# Sensor.net
KiCad netlist of a schematic drawn in Altium Designer
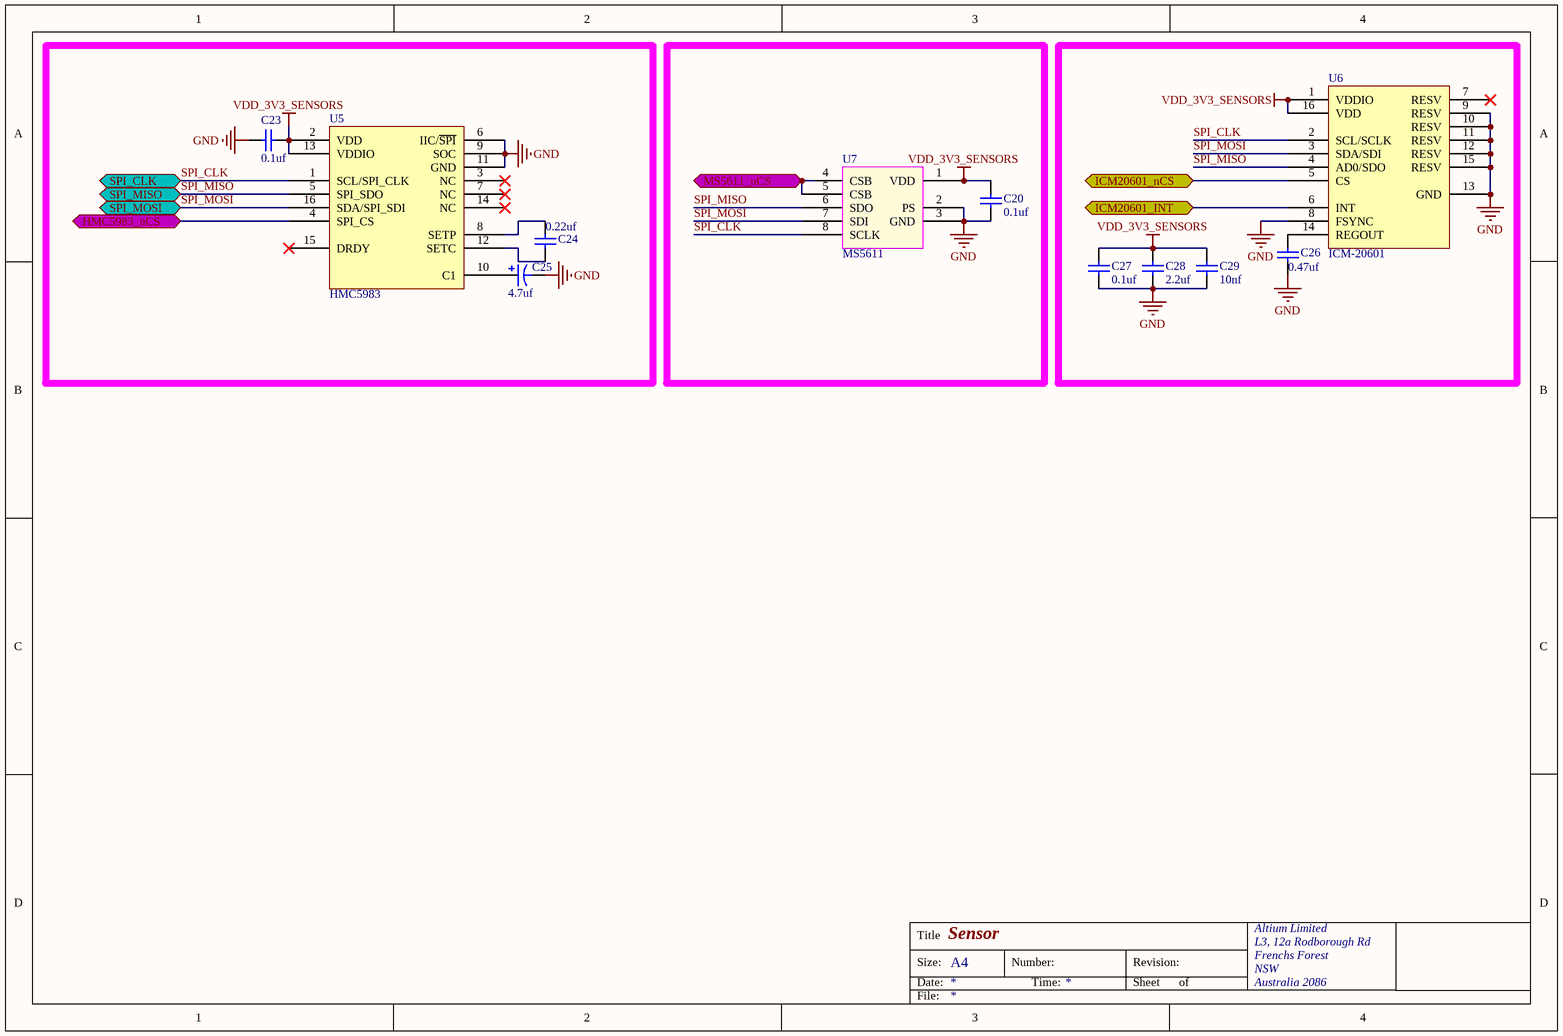
[diagram p0: Sensor.SchDoc]

(export (version "E")
  (design (tool "Eeschema 10.0.6"))
  (components
    (comp (ref "C20")
      (value "0.1uf")
      (footprint "0603AC")
      (description "Capacitor")
      (fields (field (name "Comment") "Cap1") (field (name "PUBLISHER") "Altium Limited"))
      (libsource (lib "Component") (part "Cap1"))
    )
    (comp (ref "C23")
      (value "0.1uf")
      (footprint "0603AC")
      (description "Capacitor")
      (fields (field (name "Comment") "Cap1") (field (name "PUBLISHER") "Altium Limited"))
      (libsource (lib "Component") (part "Cap1"))
    )
    (comp (ref "C24")
      (value "0.22uf")
      (footprint "0603AC")
      (description "Capacitor")
      (fields (field (name "Comment") "Cap1") (field (name "PUBLISHER") "Altium Limited"))
      (libsource (lib "Component") (part "Cap1"))
    )
    (comp (ref "C25")
      (value "4.7uf")
      (footprint "0603AC")
      (description "Polarized Capacitor (Axial)")
      (fields (field (name "Comment") "Cap Pol1") (field (name "PUBLISHER") "Altium Limited"))
      (libsource (lib "Component") (part "Cap Pol1"))
    )
    (comp (ref "C26")
      (value "0.47uf")
      (footprint "0603AC")
      (description "Capacitor")
      (fields (field (name "Comment") "Cap1") (field (name "PUBLISHER") "Altium Limited"))
      (libsource (lib "Component") (part "Cap1"))
    )
    (comp (ref "C27")
      (value "0.1uf")
      (footprint "0603AC")
      (description "Capacitor")
      (fields (field (name "Comment") "Cap1") (field (name "PUBLISHER") "Altium Limited"))
      (libsource (lib "Component") (part "Cap1"))
    )
    (comp (ref "C28")
      (value "2.2uf")
      (footprint "0603AC")
      (description "Capacitor")
      (fields (field (name "Comment") "Cap1") (field (name "PUBLISHER") "Altium Limited"))
      (libsource (lib "Component") (part "Cap1"))
    )
    (comp (ref "C29")
      (value "10nf")
      (footprint "0603AC")
      (description "Capacitor")
      (fields (field (name "Comment") "Cap1") (field (name "PUBLISHER") "Altium Limited"))
      (libsource (lib "Component") (part "Cap1"))
    )
    (comp (ref "U5") (value "HMC5983") (footprint "LPCC-16PIN") (libsource (lib "Sensor") (part "HMC5983")))
    (comp (ref "U6")
      (value "ICM-20601")
      (footprint "LGA-16PIN")
      (libsource (lib "Sensor") (part "ICM-20601"))
    )
    (comp (ref "U7") (value "MS5611") (footprint "MS5611") (libsource (lib "Sensor") (part "MS5611")))
  )
  (nets
    (net (code "1") (name "/HMC5983_nCS") (class "Default")
      (node (ref "U5") (pin "4") (pinfunction "SPI_CS_4") (pintype "passive"))
    )
    (net (code "2") (name "/ICM20601_INT") (class "Default")
      (node (ref "U6") (pin "6") (pinfunction "INT_6") (pintype "passive"))
    )
    (net (code "3") (name "/ICM20601_nCS") (class "Default")
      (node (ref "U6") (pin "5") (pinfunction "CS_5") (pintype "passive"))
    )
    (net (code "4") (name "/MS5611_nCS") (class "Default")
      (node (ref "U7") (pin "4") (pinfunction "CSB_4") (pintype "passive"))
      (node (ref "U7") (pin "5") (pinfunction "CSB_5") (pintype "passive"))
    )
    (net (code "5") (name "/SPI_CLK") (class "Default")
      (node (ref "U5") (pin "1") (pinfunction "SCL/SPI_CLK_1") (pintype "passive"))
      (node (ref "U6") (pin "2") (pinfunction "SCL/SCLK_2") (pintype "passive"))
      (node (ref "U7") (pin "8") (pinfunction "SCLK_8") (pintype "passive"))
    )
    (net (code "6") (name "/SPI_MISO") (class "Default")
      (node (ref "U5") (pin "5") (pinfunction "SPI_SDO_5") (pintype "passive"))
      (node (ref "U6") (pin "4") (pinfunction "AD0/SDO_4") (pintype "passive"))
      (node (ref "U7") (pin "6") (pinfunction "SDO_6") (pintype "passive"))
    )
    (net (code "7") (name "/SPI_MOSI") (class "Default")
      (node (ref "U5") (pin "16") (pinfunction "SDA/SPI_SDI_16") (pintype "passive"))
      (node (ref "U6") (pin "3") (pinfunction "SDA/SDI_3") (pintype "passive"))
      (node (ref "U7") (pin "7") (pinfunction "SDI_7") (pintype "passive"))
    )
    (net (code "8") (name "GND") (class "Default")
      (node (ref "C20") (pin "2") (pinfunction "2_2") (pintype "passive"))
      (node (ref "C23") (pin "2") (pinfunction "2_2") (pintype "passive"))
      (node (ref "C25") (pin "2") (pinfunction "2_2") (pintype "passive"))
      (node (ref "C26") (pin "1") (pinfunction "1_1") (pintype "passive"))
      (node (ref "C27") (pin "2") (pinfunction "2_2") (pintype "passive"))
      (node (ref "C28") (pin "2") (pinfunction "2_2") (pintype "passive"))
      (node (ref "C29") (pin "2") (pinfunction "2_2") (pintype "passive"))
      (node (ref "U5") (pin "11") (pinfunction "GND_11") (pintype "passive"))
      (node (ref "U5") (pin "6") (pinfunction "IIC/~{SPI}_6") (pintype "passive"))
      (node (ref "U5") (pin "9") (pinfunction "SOC_9") (pintype "passive"))
      (node (ref "U6") (pin "10") (pinfunction "RESV_10") (pintype "passive"))
      (node (ref "U6") (pin "11") (pinfunction "RESV_11") (pintype "passive"))
      (node (ref "U6") (pin "12") (pinfunction "RESV_12") (pintype "passive"))
      (node (ref "U6") (pin "13") (pinfunction "GND_13") (pintype "passive"))
      (node (ref "U6") (pin "15") (pinfunction "RESV_15") (pintype "passive"))
      (node (ref "U6") (pin "8") (pinfunction "FSYNC_8") (pintype "passive"))
      (node (ref "U6") (pin "9") (pinfunction "RESV_9") (pintype "passive"))
      (node (ref "U7") (pin "2") (pinfunction "PS_2") (pintype "passive"))
      (node (ref "U7") (pin "3") (pinfunction "GND_3") (pintype "passive"))
    )
    (net (code "9") (name "Net-(U5-C1)") (class "Default")
      (node (ref "C25") (pin "1") (pinfunction "1_1") (pintype "passive"))
      (node (ref "U5") (pin "10") (pinfunction "C1_10") (pintype "passive"))
    )
    (net (code "10") (name "Net-(U5-SETC)") (class "Default")
      (node (ref "C24") (pin "1") (pinfunction "1_1") (pintype "passive"))
      (node (ref "U5") (pin "12") (pinfunction "SETC_12") (pintype "passive"))
    )
    (net (code "11") (name "Net-(U5-SETP)") (class "Default")
      (node (ref "C24") (pin "2") (pinfunction "2_2") (pintype "passive"))
      (node (ref "U5") (pin "8") (pinfunction "SETP_8") (pintype "passive"))
    )
    (net (code "12") (name "Net-(U6-REGOUT)") (class "Default")
      (node (ref "C26") (pin "2") (pinfunction "2_2") (pintype "passive"))
      (node (ref "U6") (pin "14") (pinfunction "REGOUT_14") (pintype "passive"))
    )
    (net (code "13") (name "VDD_3V3_SENSORS") (class "Default")
      (node (ref "C20") (pin "1") (pinfunction "1_1") (pintype "passive"))
      (node (ref "C23") (pin "1") (pinfunction "1_1") (pintype "passive"))
      (node (ref "C27") (pin "1") (pinfunction "1_1") (pintype "passive"))
      (node (ref "C28") (pin "1") (pinfunction "1_1") (pintype "passive"))
      (node (ref "C29") (pin "1") (pinfunction "1_1") (pintype "passive"))
      (node (ref "U5") (pin "13") (pinfunction "VDDIO_13") (pintype "passive"))
      (node (ref "U5") (pin "2") (pinfunction "VDD_2") (pintype "passive"))
      (node (ref "U6") (pin "1") (pinfunction "VDDIO_1") (pintype "passive"))
      (node (ref "U6") (pin "16") (pinfunction "VDD_16") (pintype "passive"))
      (node (ref "U7") (pin "1") (pinfunction "VDD_1") (pintype "passive"))
    )
    (net (code "14") (name "unconnected-(U5-DRDY-Pad15)") (class "Default")
      (node (ref "U5") (pin "15") (pinfunction "DRDY_15") (pintype "passive+no_connect"))
    )
    (net (code "15") (name "unconnected-(U5-NC-Pad3)") (class "Default")
      (node (ref "U5") (pin "3") (pinfunction "NC_3") (pintype "passive+no_connect"))
    )
    (net (code "16") (name "unconnected-(U5-NC-Pad7)") (class "Default")
      (node (ref "U5") (pin "7") (pinfunction "NC_7") (pintype "passive+no_connect"))
    )
    (net (code "17") (name "unconnected-(U5-NC-Pad14)") (class "Default")
      (node (ref "U5") (pin "14") (pinfunction "NC_14") (pintype "passive+no_connect"))
    )
    (net (code "18") (name "unconnected-(U6-RESV-Pad7)") (class "Default")
      (node (ref "U6") (pin "7") (pinfunction "RESV_7") (pintype "passive+no_connect"))
    )
  )
)
